# MING_RTD.net
KiCad netlist of a schematic drawn in Altium Designer
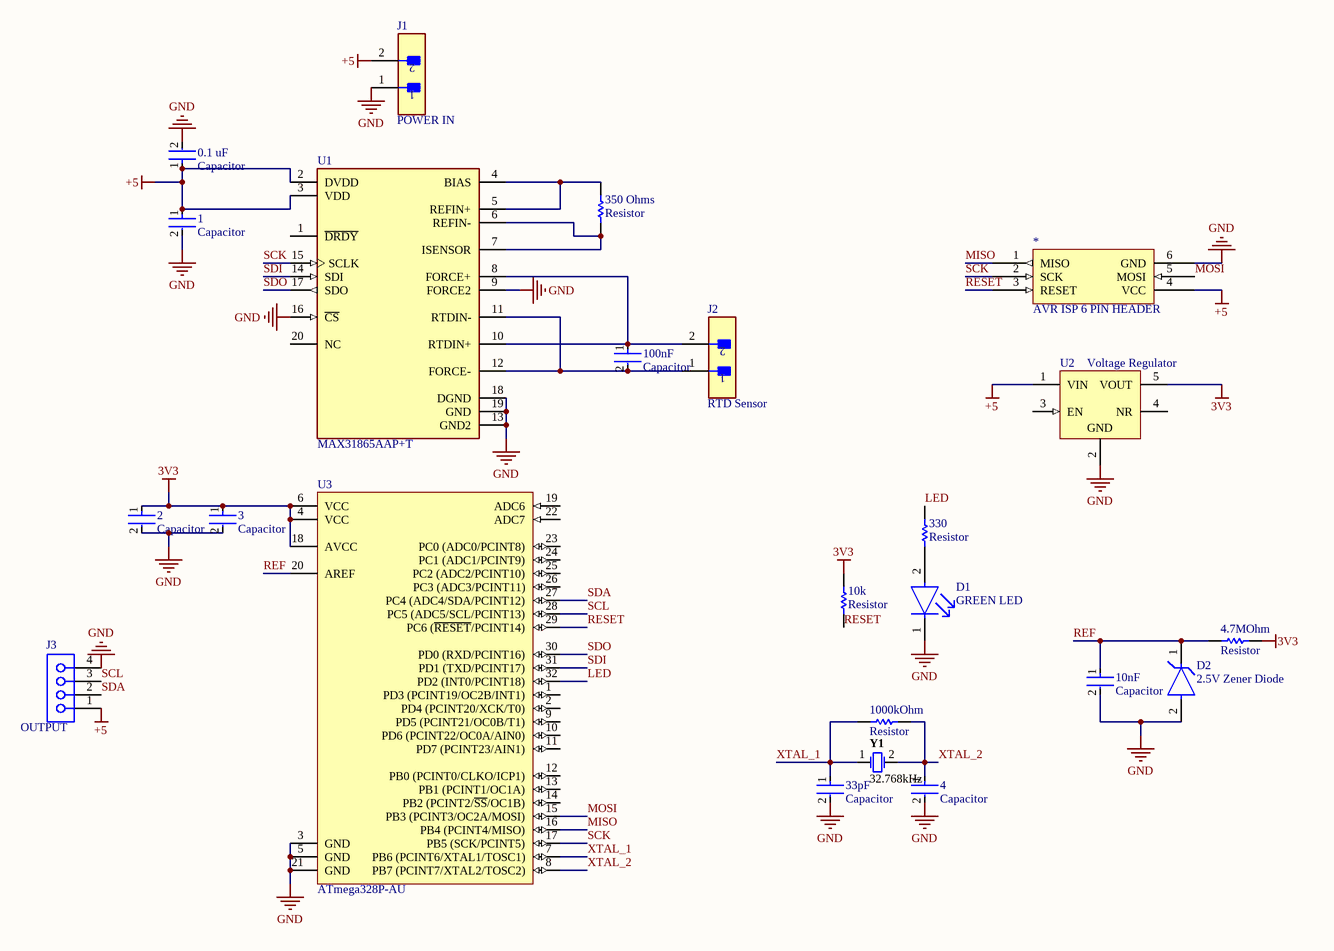
[diagram p0: MING RTD.SchDoc]

(export (version "E")
  (design (tool "Eeschema 10.0.6"))
  (components
    (comp (ref "*") (value "AVR ISP 6 PIN HEADER") (libsource (lib "Main") (part "AVR ISP 6 PIN HEADER")))
    (comp (ref "0.1 uF")
      (value "Capacitor")
      (footprint "FP-C0402-BB-MFG")
      (description "CAP CER 0.1UF 10V X5R 0402")
      (fields (field (name "MANUFACTURER") "Kemet") (field (name "TOLERANCE") "0.1"))
      (libsource (lib "Altium Content Vault") (part "b4654b650e69147ec39a6b967a45e02"))
    )
    (comp (ref "1")
      (value "Capacitor")
      (footprint "FP-C0402-BB-MFG")
      (description "CAP CER 0.1UF 10V X5R 0402")
      (fields (field (name "MANUFACTURER") "Kemet") (field (name "TOLERANCE") "0.1"))
      (libsource (lib "Altium Content Vault") (part "b4654b650e69147ec39a6b967a45e02"))
    )
    (comp (ref "2")
      (value "Capacitor")
      (footprint "FP-C0402-BB-MFG")
      (description "CAP CER 0.1UF 10V X5R 0402")
      (fields (field (name "MANUFACTURER") "Kemet") (field (name "TOLERANCE") "0.1"))
      (libsource (lib "Altium Content Vault") (part "b4654b650e69147ec39a6b967a45e02"))
    )
    (comp (ref "3")
      (value "Capacitor")
      (footprint "FP-C0402-BB-MFG")
      (description "CAP CER 0.1UF 10V X5R 0402")
      (fields (field (name "MANUFACTURER") "Kemet") (field (name "TOLERANCE") "0.1"))
      (libsource (lib "Altium Content Vault") (part "b4654b650e69147ec39a6b967a45e02"))
    )
    (comp (ref "4")
      (value "Capacitor")
      (footprint "FP-C0402-BB-MFG")
      (description "CAP CER 0.1UF 10V X5R 0402")
      (fields (field (name "MANUFACTURER") "Kemet") (field (name "TOLERANCE") "0.1"))
      (libsource (lib "Altium Content Vault") (part "b4654b650e69147ec39a6b967a45e02"))
    )
    (comp (ref "4.7MOhm")
      (value "Resistor")
      (footprint "RESC1609X50X30NL8T20")
      (description "Chip Resistor, 0 Ohm, Jumper, 100 mW, -55 to 155 degC, 0603 (1608 Metric), RoHS, Tape and Reel")
      (fields (field (name "MANUFACTURER") "Vishay Semiconductor"))
      (libsource (lib "Altium Content Vault") (part "RES-2"))
    )
    (comp (ref "10k")
      (value "Resistor")
      (footprint "RESC1609X50X30NL8T20")
      (description "Chip Resistor, 0 Ohm, Jumper, 100 mW, -55 to 155 degC, 0603 (1608 Metric), RoHS, Tape and Reel")
      (fields (field (name "MANUFACTURER") "Vishay Semiconductor"))
      (libsource (lib "Altium Content Vault") (part "RES-2"))
    )
    (comp (ref "10nF")
      (value "Capacitor")
      (footprint "FP-C0402-BB-MFG")
      (description "CAP CER 0.1UF 10V X5R 0402")
      (fields (field (name "MANUFACTURER") "Kemet") (field (name "TOLERANCE") "0.1"))
      (libsource (lib "Altium Content Vault") (part "b4654b650e69147ec39a6b967a45e02"))
    )
    (comp (ref "33pF")
      (value "Capacitor")
      (footprint "FP-C0402-BB-MFG")
      (description "CAP CER 0.1UF 10V X5R 0402")
      (fields (field (name "MANUFACTURER") "Kemet") (field (name "TOLERANCE") "0.1"))
      (libsource (lib "Altium Content Vault") (part "b4654b650e69147ec39a6b967a45e02"))
    )
    (comp (ref "100nF")
      (value "Capacitor")
      (footprint "FP-C0402-BB-MFG")
      (description "CAP CER 0.1UF 10V X5R 0402")
      (fields (field (name "MANUFACTURER") "Kemet") (field (name "TOLERANCE") "0.1"))
      (libsource (lib "Altium Content Vault") (part "b4654b650e69147ec39a6b967a45e02"))
    )
    (comp (ref "330")
      (value "Resistor")
      (footprint "RESC1609X50X30NL8T20")
      (description "Chip Resistor, 0 Ohm, Jumper, 100 mW, -55 to 155 degC, 0603 (1608 Metric), RoHS, Tape and Reel")
      (fields (field (name "MANUFACTURER") "Vishay Semiconductor"))
      (libsource (lib "Altium Content Vault") (part "RES-2"))
    )
    (comp (ref "350 Ohms")
      (value "Resistor")
      (footprint "RESC1609X50X30NL8T20")
      (description "Chip Resistor, 0 Ohm, Jumper, 100 mW, -55 to 155 degC, 0603 (1608 Metric), RoHS, Tape and Reel")
      (fields (field (name "MANUFACTURER") "Vishay Semiconductor"))
      (libsource (lib "Altium Content Vault") (part "RES-2"))
    )
    (comp (ref "1000kOhm")
      (value "Resistor")
      (footprint "RESC1609X50X30NL8T20")
      (description "Chip Resistor, 0 Ohm, Jumper, 100 mW, -55 to 155 degC, 0603 (1608 Metric), RoHS, Tape and Reel")
      (fields (field (name "MANUFACTURER") "Vishay Semiconductor"))
      (libsource (lib "Altium Content Vault") (part "RES-2"))
    )
    (comp (ref "D1")
      (value "GREEN LED")
      (footprint "FP-597-3301-507F-MFG")
      (description "LED GREEN CLEAR 1208 SMD")
      (fields
        (field (name "OCTOPART") "https://octopart.com/597-3301-507f-dialight-117926")
        (field (name "MANUFACTURER") "Dialight")
      )
      (libsource (lib "Altium Content Vault") (part "8706943c75ba83719d021d2fdc84c58"))
    )
    (comp (ref "D2")
      (value "2.5V Zener Diode")
      (footprint "FP-425-04-IPC_B")
      (description "DIODE ZENER 2.5V 500MW SOD123")
      (fields (field (name "TOLERANCE") "5%"))
      (libsource (lib "Altium Content Vault") (part "f813f71cba58e380607f5dd3caf9714"))
    )
    (comp (ref "J1")
      (value "POWER IN")
      (footprint "FP-B2B-XH-A_LF_SN-MFG")
      (description "CONN HEADER VERT 2POS 2.5MM")
      (libsource (lib "Altium Content Vault") (part "3bc925449376181038e59eaffc5286c"))
    )
    (comp (ref "J2")
      (value "RTD Sensor")
      (footprint "FP-B2B-XH-A_LF_SN-MFG")
      (description "CONN HEADER VERT 2POS 2.5MM")
      (libsource (lib "Altium Content Vault") (part "3bc925449376181038e59eaffc5286c"))
    )
    (comp (ref "J3")
      (value "OUTPUT")
      (footprint "SMTC-SLW-104-01-X-S")
      (fields (field (name "MANUFACTURER") "Samtec") (field (name "PARTNUMBER") "SLW-104-01-G-S"))
      (libsource (lib "Altium Content Vault") (part "SMTC-SLW-104-01-X-S"))
    )
    (comp (ref "U1")
      (value "MAX31865AAP+T")
      (footprint "FP-A20-1-MFG")
      (description "IC RTD TO DIGITAL CONVERT 20SSOP")
      (libsource (lib "Altium Content Vault") (part "4226c690f7a4accb91cfe97fa6b1631"))
    )
    (comp (ref "U2")
      (value "Voltage Regulator")
      (footprint "DBV0005A_N")
      (fields (field (name "MANUFACTURER") "Texas Instruments") (field (name "PARTNUMBER") "REG102NA-3.3/3K"))
      (libsource (lib "Altium Content Vault") (part "TI-REG1XX-XXXDBV5"))
    )
    (comp (ref "U3")
      (value "ATmega328P-AU")
      (footprint "32A_L")
      (libsource (lib "Main") (part "ATmega328P-AU"))
    )
    (comp (ref "Y1")
      (value "32.768kHz")
      (footprint "TXC-9HT10_V")
      (description "Tuning Fork, 32.768 KHz, -40 to 85 degC, 2-Pin SMD, RoHS, Tape and Reel")
      (fields (field (name "TOLERANCE") "1%"))
      (libsource (lib "Altium Content Vault") (part "XTAL-1-2-2"))
    )
  )
  (nets
    (net (code "1") (name "+5") (class "Default")
      (node (ref "*") (pin "4") (pinfunction "VCC_4") (pintype "power_in"))
      (node (ref "0.1 uF") (pin "1") (pinfunction "1_1") (pintype "passive"))
      (node (ref "1") (pin "1") (pinfunction "1_1") (pintype "passive"))
      (node (ref "J1") (pin "2") (pinfunction "2_2") (pintype "passive"))
      (node (ref "J3") (pin "1") (pinfunction "1_1") (pintype "passive"))
      (node (ref "U1") (pin "2") (pinfunction "DVDD_2") (pintype "power_in"))
      (node (ref "U1") (pin "3") (pinfunction "VDD_3") (pintype "power_in"))
      (node (ref "U2") (pin "1") (pinfunction "VIN_1") (pintype "power_in"))
    )
    (net (code "2") (name "/LED") (class "Default")
      (node (ref "330") (pin "1") (pinfunction "1_1") (pintype "passive"))
      (node (ref "U3") (pin "32") (pinfunction "PD2_(INT0/PCINT18)_32") (pintype "bidirectional"))
    )
    (net (code "3") (name "/MISO") (class "Default")
      (node (ref "*") (pin "1") (pinfunction "MISO_1") (pintype "output"))
      (node (ref "U3") (pin "16") (pinfunction "PB4_(PCINT4/MISO)_16") (pintype "bidirectional"))
    )
    (net (code "4") (name "/MOSI") (class "Default")
      (node (ref "*") (pin "5") (pinfunction "MOSI_5") (pintype "input"))
      (node (ref "U3") (pin "15") (pinfunction "PB3_(PCINT3/OC2A/MOSI)_15") (pintype "bidirectional"))
    )
    (net (code "5") (name "/REF") (class "Default")
      (node (ref "10nF") (pin "1") (pinfunction "1_1") (pintype "passive"))
      (node (ref "4.7MOhm") (pin "2") (pinfunction "2_2") (pintype "passive"))
      (node (ref "D2") (pin "1") (pinfunction "C_1") (pintype "passive"))
      (node (ref "U3") (pin "20") (pinfunction "AREF_20") (pintype "passive"))
    )
    (net (code "6") (name "/RESET") (class "Default")
      (node (ref "*") (pin "3") (pinfunction "RESET_3") (pintype "input"))
      (node (ref "10k") (pin "1") (pinfunction "1_1") (pintype "passive"))
      (node (ref "U3") (pin "29") (pinfunction "PC6_(~{RESET}/PCINT14)_29") (pintype "bidirectional"))
    )
    (net (code "7") (name "/SCK") (class "Default")
      (node (ref "*") (pin "2") (pinfunction "SCK_2") (pintype "input"))
      (node (ref "U1") (pin "15") (pinfunction "SCLK_15") (pintype "input"))
      (node (ref "U3") (pin "17") (pinfunction "PB5_(SCK/PCINT5)_17") (pintype "bidirectional"))
    )
    (net (code "8") (name "/SCL") (class "Default")
      (node (ref "J3") (pin "3") (pinfunction "3_3") (pintype "passive"))
      (node (ref "U3") (pin "28") (pinfunction "PC5_(ADC5/SCL/PCINT13)_28") (pintype "bidirectional"))
    )
    (net (code "9") (name "/SDA") (class "Default")
      (node (ref "J3") (pin "2") (pinfunction "2_2") (pintype "passive"))
      (node (ref "U3") (pin "27") (pinfunction "PC4_(ADC4/SDA/PCINT12)_27") (pintype "bidirectional"))
    )
    (net (code "10") (name "/SDI") (class "Default")
      (node (ref "U1") (pin "14") (pinfunction "SDI_14") (pintype "input"))
      (node (ref "U3") (pin "31") (pinfunction "PD1_(TXD/PCINT17)_31") (pintype "bidirectional"))
    )
    (net (code "11") (name "/SDO") (class "Default")
      (node (ref "U1") (pin "17") (pinfunction "SDO_17") (pintype "output"))
      (node (ref "U3") (pin "30") (pinfunction "PD0_(RXD/PCINT16)_30") (pintype "bidirectional"))
    )
    (net (code "12") (name "/XTAL_1") (class "Default")
      (node (ref "1000kOhm") (pin "2") (pinfunction "2_2") (pintype "passive"))
      (node (ref "33pF") (pin "1") (pinfunction "1_1") (pintype "passive"))
      (node (ref "U3") (pin "7") (pinfunction "PB6_(PCINT6/XTAL1/TOSC1)_7") (pintype "bidirectional"))
      (node (ref "Y1") (pin "1") (pinfunction "1_1") (pintype "passive"))
    )
    (net (code "13") (name "/XTAL_2") (class "Default")
      (node (ref "1000kOhm") (pin "1") (pinfunction "1_1") (pintype "passive"))
      (node (ref "4") (pin "1") (pinfunction "1_1") (pintype "passive"))
      (node (ref "U3") (pin "8") (pinfunction "PB7_(PCINT7/XTAL2/TOSC2)_8") (pintype "bidirectional"))
      (node (ref "Y1") (pin "2") (pinfunction "2_2") (pintype "passive"))
    )
    (net (code "14") (name "3V3") (class "Default")
      (node (ref "10k") (pin "2") (pinfunction "2_2") (pintype "passive"))
      (node (ref "2") (pin "1") (pinfunction "1_1") (pintype "passive"))
      (node (ref "3") (pin "1") (pinfunction "1_1") (pintype "passive"))
      (node (ref "4.7MOhm") (pin "1") (pinfunction "1_1") (pintype "passive"))
      (node (ref "U2") (pin "5") (pinfunction "VOUT_5") (pintype "power_in"))
      (node (ref "U3") (pin "18") (pinfunction "AVCC_18") (pintype "power_in"))
      (node (ref "U3") (pin "4") (pinfunction "VCC_4") (pintype "power_in"))
      (node (ref "U3") (pin "6") (pinfunction "VCC_6") (pintype "power_in"))
    )
    (net (code "15") (name "GND") (class "Default")
      (node (ref "*") (pin "6") (pinfunction "GND_6") (pintype "power_in"))
      (node (ref "0.1 uF") (pin "2") (pinfunction "2_2") (pintype "passive"))
      (node (ref "1") (pin "2") (pinfunction "2_2") (pintype "passive"))
      (node (ref "10nF") (pin "2") (pinfunction "2_2") (pintype "passive"))
      (node (ref "2") (pin "2") (pinfunction "2_2") (pintype "passive"))
      (node (ref "3") (pin "2") (pinfunction "2_2") (pintype "passive"))
      (node (ref "33pF") (pin "2") (pinfunction "2_2") (pintype "passive"))
      (node (ref "4") (pin "2") (pinfunction "2_2") (pintype "passive"))
      (node (ref "D1") (pin "1") (pinfunction "C_1") (pintype "passive"))
      (node (ref "D2") (pin "2") (pinfunction "A_2") (pintype "passive"))
      (node (ref "J1") (pin "1") (pinfunction "1_1") (pintype "passive"))
      (node (ref "J3") (pin "4") (pinfunction "4_4") (pintype "passive"))
      (node (ref "U1") (pin "13") (pinfunction "GND2_13") (pintype "power_in"))
      (node (ref "U1") (pin "16") (pinfunction "~{CS}_16") (pintype "input"))
      (node (ref "U1") (pin "18") (pinfunction "DGND_18") (pintype "power_in"))
      (node (ref "U1") (pin "19") (pinfunction "GND_19") (pintype "power_in"))
      (node (ref "U1") (pin "9") (pinfunction "FORCE2_9") (pintype "passive"))
      (node (ref "U2") (pin "2") (pinfunction "GND_2") (pintype "power_in"))
      (node (ref "U3") (pin "21") (pinfunction "GND_21") (pintype "power_in"))
      (node (ref "U3") (pin "3") (pinfunction "GND_3") (pintype "power_in"))
      (node (ref "U3") (pin "5") (pinfunction "GND_5") (pintype "power_in"))
    )
    (net (code "16") (name "Net-(D1-A)") (class "Default")
      (node (ref "330") (pin "2") (pinfunction "2_2") (pintype "passive"))
      (node (ref "D1") (pin "2") (pinfunction "A_2") (pintype "passive"))
    )
    (net (code "17") (name "Net-(U1-BIAS)") (class "Default")
      (node (ref "350 Ohms") (pin "2") (pinfunction "2_2") (pintype "passive"))
      (node (ref "U1") (pin "4") (pinfunction "BIAS_4") (pintype "passive"))
      (node (ref "U1") (pin "5") (pinfunction "REFIN+_5") (pintype "passive"))
    )
    (net (code "18") (name "Net-(U1-FORCE+)") (class "Default")
      (node (ref "100nF") (pin "1") (pinfunction "1_1") (pintype "passive"))
      (node (ref "J2") (pin "2") (pinfunction "2_2") (pintype "passive"))
      (node (ref "U1") (pin "10") (pinfunction "RTDIN+_10") (pintype "passive"))
      (node (ref "U1") (pin "8") (pinfunction "FORCE+_8") (pintype "passive"))
    )
    (net (code "19") (name "Net-(U1-FORCE-)") (class "Default")
      (node (ref "100nF") (pin "2") (pinfunction "2_2") (pintype "passive"))
      (node (ref "J2") (pin "1") (pinfunction "1_1") (pintype "passive"))
      (node (ref "U1") (pin "11") (pinfunction "RTDIN-_11") (pintype "passive"))
      (node (ref "U1") (pin "12") (pinfunction "FORCE-_12") (pintype "passive"))
    )
    (net (code "20") (name "Net-(U1-ISENSOR)") (class "Default")
      (node (ref "350 Ohms") (pin "1") (pinfunction "1_1") (pintype "passive"))
      (node (ref "U1") (pin "6") (pinfunction "REFIN-_6") (pintype "passive"))
      (node (ref "U1") (pin "7") (pinfunction "ISENSOR_7") (pintype "passive"))
    )
    (net (code "21") (name "unconnected-(U1-NC-Pad20)") (class "Default")
      (node (ref "U1") (pin "20") (pinfunction "NC_20") (pintype "passive"))
    )
    (net (code "22") (name "unconnected-(U1-~{DRDY}-Pad1)") (class "Default")
      (node (ref "U1") (pin "1") (pinfunction "~{DRDY}_1") (pintype "passive"))
    )
    (net (code "23") (name "unconnected-(U2-EN-Pad3)") (class "Default")
      (node (ref "U2") (pin "3") (pinfunction "EN_3") (pintype "input"))
    )
    (net (code "24") (name "unconnected-(U2-NR-Pad4)") (class "Default")
      (node (ref "U2") (pin "4") (pinfunction "NR_4") (pintype "passive"))
    )
    (net (code "25") (name "unconnected-(U3-ADC6-Pad19)") (class "Default")
      (node (ref "U3") (pin "19") (pinfunction "ADC6_19") (pintype "input"))
    )
    (net (code "26") (name "unconnected-(U3-ADC7-Pad22)") (class "Default")
      (node (ref "U3") (pin "22") (pinfunction "ADC7_22") (pintype "input"))
    )
    (net (code "27") (name "unconnected-(U3-PB0_(PCINT0{slash}CLKO{slash}ICP1)-Pad12)") (class "Default")
      (node (ref "U3") (pin "12") (pinfunction "PB0_(PCINT0/CLKO/ICP1)_12") (pintype "bidirectional"))
    )
    (net (code "28") (name "unconnected-(U3-PB1_(PCINT1{slash}OC1A)-Pad13)") (class "Default")
      (node (ref "U3") (pin "13") (pinfunction "PB1_(PCINT1/OC1A)_13") (pintype "bidirectional"))
    )
    (net (code "29") (name "unconnected-(U3-PB2_(PCINT2{slash}~{SS}{slash}OC1B)-Pad14)") (class "Default")
      (node (ref "U3") (pin "14") (pinfunction "PB2_(PCINT2/~{SS}/OC1B)_14") (pintype "bidirectional"))
    )
    (net (code "30") (name "unconnected-(U3-PC0_(ADC0{slash}PCINT8)-Pad23)") (class "Default")
      (node (ref "U3") (pin "23") (pinfunction "PC0_(ADC0/PCINT8)_23") (pintype "bidirectional"))
    )
    (net (code "31") (name "unconnected-(U3-PC1_(ADC1{slash}PCINT9)-Pad24)") (class "Default")
      (node (ref "U3") (pin "24") (pinfunction "PC1_(ADC1/PCINT9)_24") (pintype "bidirectional"))
    )
    (net (code "32") (name "unconnected-(U3-PC2_(ADC2{slash}PCINT10)-Pad25)") (class "Default")
      (node (ref "U3") (pin "25") (pinfunction "PC2_(ADC2/PCINT10)_25") (pintype "bidirectional"))
    )
    (net (code "33") (name "unconnected-(U3-PC3_(ADC3{slash}PCINT11)-Pad26)") (class "Default")
      (node (ref "U3") (pin "26") (pinfunction "PC3_(ADC3/PCINT11)_26") (pintype "bidirectional"))
    )
    (net (code "34") (name "unconnected-(U3-PD3_(PCINT19{slash}OC2B{slash}INT1)-Pad1)") (class "Default")
      (node (ref "U3") (pin "1") (pinfunction "PD3_(PCINT19/OC2B/INT1)_1") (pintype "bidirectional"))
    )
    (net (code "35") (name "unconnected-(U3-PD4_(PCINT20{slash}XCK{slash}T0)-Pad2)") (class "Default")
      (node (ref "U3") (pin "2") (pinfunction "PD4_(PCINT20/XCK/T0)_2") (pintype "bidirectional"))
    )
    (net (code "36") (name "unconnected-(U3-PD5_(PCINT21{slash}OC0B{slash}T1)-Pad9)") (class "Default")
      (node (ref "U3") (pin "9") (pinfunction "PD5_(PCINT21/OC0B/T1)_9") (pintype "bidirectional"))
    )
    (net (code "37") (name "unconnected-(U3-PD6_(PCINT22{slash}OC0A{slash}AIN0)-Pad10)") (class "Default")
      (node (ref "U3") (pin "10") (pinfunction "PD6_(PCINT22/OC0A/AIN0)_10") (pintype "bidirectional"))
    )
    (net (code "38") (name "unconnected-(U3-PD7_(PCINT23{slash}AIN1)-Pad11)") (class "Default")
      (node (ref "U3") (pin "11") (pinfunction "PD7_(PCINT23/AIN1)_11") (pintype "bidirectional"))
    )
  )
)
